# Relay_Board_2nd_Iteration.net
KiCad netlist of a schematic drawn in EAGLE
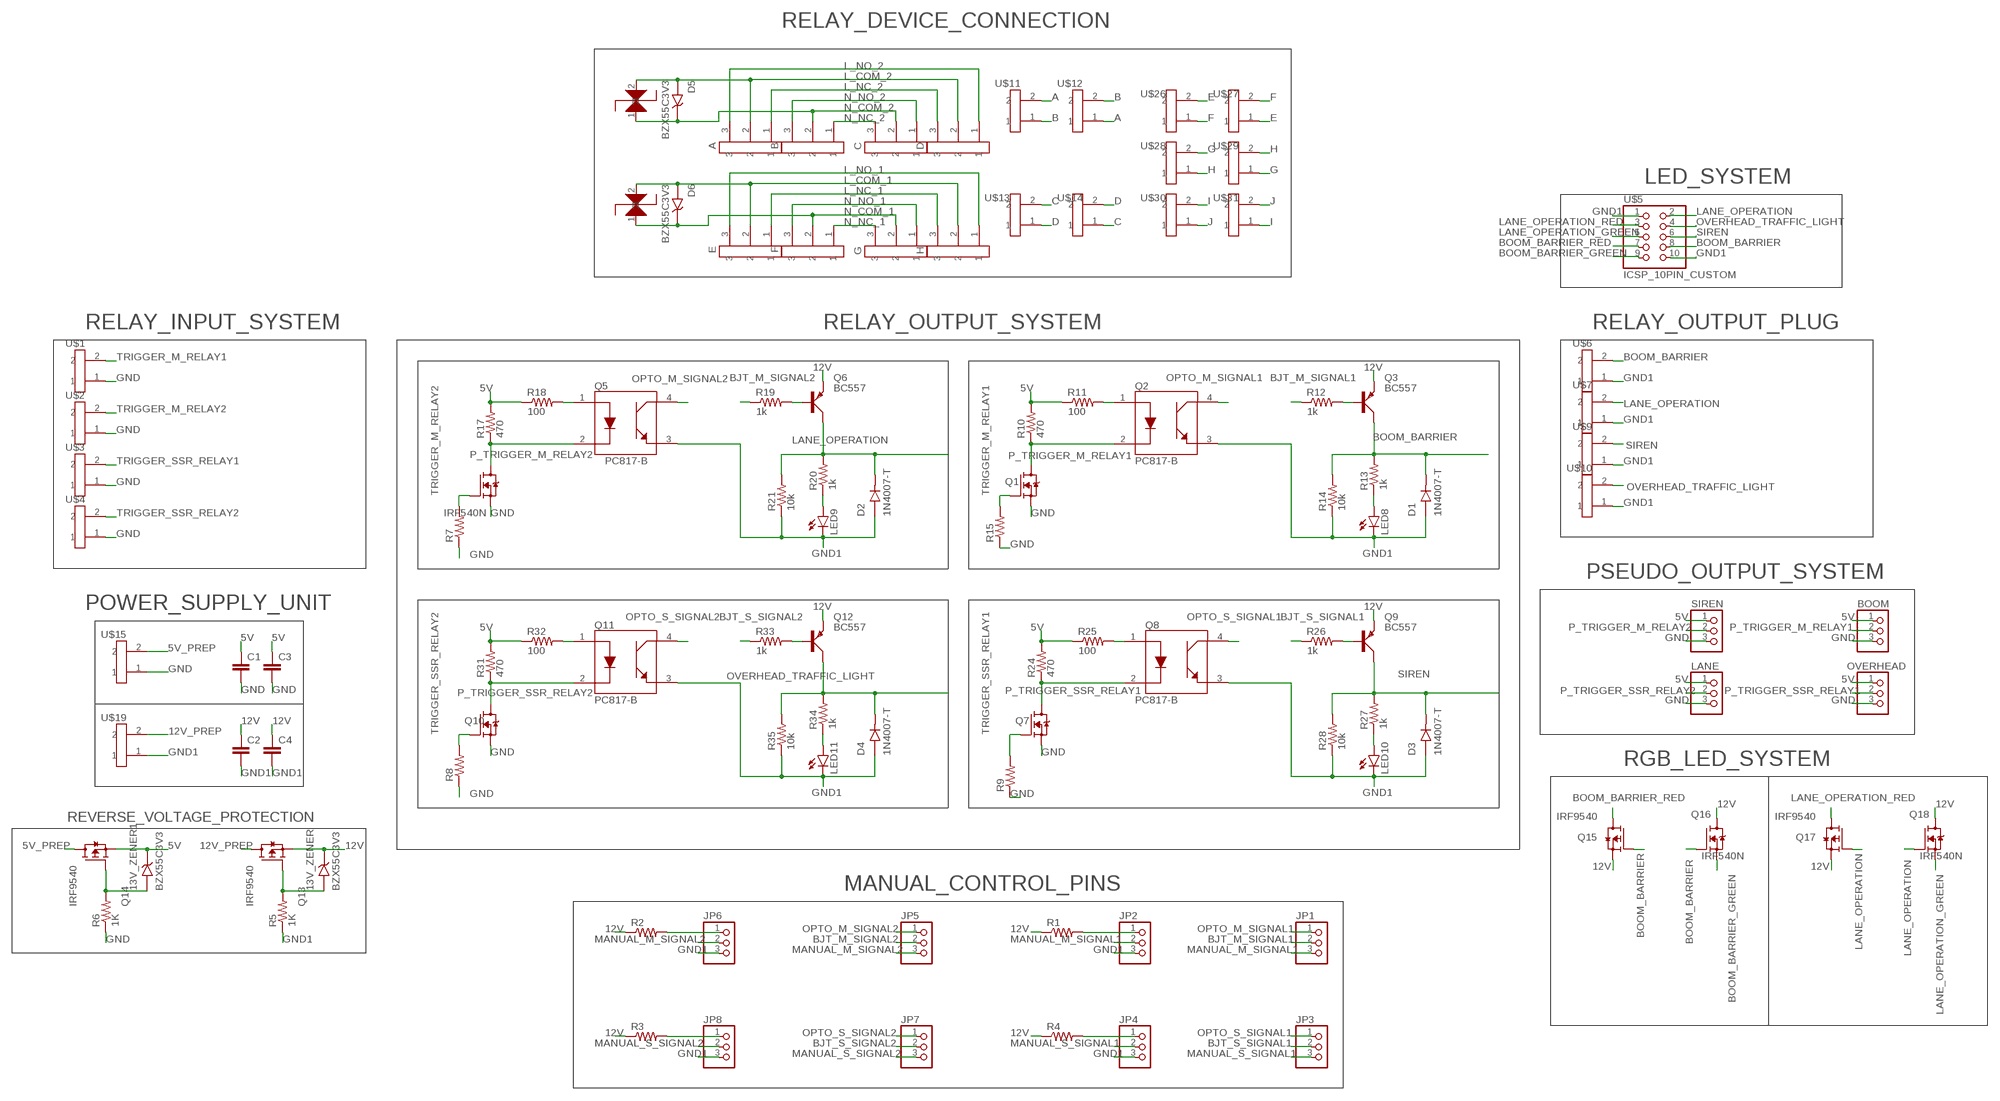
[diagram p0: schematic, sheet 1]

(export (version "E")
  (design (tool "Eeschema 10.0.6"))
  (components
    (comp (ref "13V_ZENER")
      (value "BZX55C3V3")
      (footprint "eagle-import:DIOAD928W47L399D179")
      (fields (field (name "MF") "Vishay Semiconductor") (field (name "MP") "BZX55C3V3-TR"))
      (libsource (lib "eagle-import") (part "BZX55C3V3"))
    )
    (comp (ref "13V_ZENER1")
      (value "BZX55C3V3")
      (footprint "eagle-import:DIOAD928W47L399D179")
      (fields (field (name "MF") "Vishay Semiconductor") (field (name "MP") "BZX55C3V3-TR"))
      (libsource (lib "eagle-import") (part "BZX55C3V3"))
    )
    (comp (ref "A")
      (value "GREEN_PLUG_3")
      (footprint "eagle-import:GREEN_PLUG_3")
      (libsource (lib "eagle-import") (part "GREEN_PLUG_3"))
    )
    (comp (ref "B")
      (value "GREEN_PLUG_3")
      (footprint "eagle-import:GREEN_PLUG_3")
      (libsource (lib "eagle-import") (part "GREEN_PLUG_3"))
    )
    (comp (ref "BOOM")
      (value "PINHD-1X3")
      (footprint "eagle-import:1X03")
      (libsource (lib "eagle-import") (part "PINHD-1X3"))
    )
    (comp (ref "C")
      (value "GREEN_PLUG_90_3")
      (footprint "eagle-import:GREEN_PLUG_90_3")
      (libsource (lib "eagle-import") (part "GREEN_PLUG_90_3"))
    )
    (comp (ref "C1")
      (value "CAPACITOR")
      (footprint "eagle-import:CAPACITOR")
      (libsource (lib "eagle-import") (part "CAPACITOR"))
    )
    (comp (ref "C2")
      (value "CAPACITOR")
      (footprint "eagle-import:CAPACITOR")
      (libsource (lib "eagle-import") (part "CAPACITOR"))
    )
    (comp (ref "C3")
      (value "CAPACITOR")
      (footprint "eagle-import:CAPACITOR")
      (libsource (lib "eagle-import") (part "CAPACITOR"))
    )
    (comp (ref "C4")
      (value "CAPACITOR")
      (footprint "eagle-import:CAPACITOR")
      (libsource (lib "eagle-import") (part "CAPACITOR"))
    )
    (comp (ref "D")
      (value "GREEN_PLUG_90_3")
      (footprint "eagle-import:GREEN_PLUG_90_3")
      (libsource (lib "eagle-import") (part "GREEN_PLUG_90_3"))
    )
    (comp (ref "D1")
      (value "1N4007-T")
      (footprint "eagle-import:DIOAD780W78L463D236")
      (fields (field (name "MF") "Diodes Incorporated"))
      (libsource (lib "eagle-import") (part "1N4007-T"))
    )
    (comp (ref "D2")
      (value "1N4007-T")
      (footprint "eagle-import:DIOAD780W78L463D236")
      (fields (field (name "MF") "Diodes Incorporated"))
      (libsource (lib "eagle-import") (part "1N4007-T"))
    )
    (comp (ref "D3")
      (value "1N4007-T")
      (footprint "eagle-import:DIOAD780W78L463D236")
      (fields (field (name "MF") "Diodes Incorporated"))
      (libsource (lib "eagle-import") (part "1N4007-T"))
    )
    (comp (ref "D4")
      (value "1N4007-T")
      (footprint "eagle-import:DIOAD780W78L463D236")
      (fields (field (name "MF") "Diodes Incorporated"))
      (libsource (lib "eagle-import") (part "1N4007-T"))
    )
    (comp (ref "D5")
      (value "BZX55C3V3")
      (footprint "eagle-import:DIOAD928W47L399D179")
      (fields (field (name "MF") "Vishay Semiconductor") (field (name "MP") "BZX55C3V3-TR"))
      (libsource (lib "eagle-import") (part "BZX55C3V3"))
    )
    (comp (ref "D6")
      (value "BZX55C3V3")
      (footprint "eagle-import:DIOAD928W47L399D179")
      (fields (field (name "MF") "Vishay Semiconductor") (field (name "MP") "BZX55C3V3-TR"))
      (libsource (lib "eagle-import") (part "BZX55C3V3"))
    )
    (comp (ref "E")
      (value "GREEN_PLUG_3")
      (footprint "eagle-import:GREEN_PLUG_3")
      (libsource (lib "eagle-import") (part "GREEN_PLUG_3"))
    )
    (comp (ref "F")
      (value "GREEN_PLUG_3")
      (footprint "eagle-import:GREEN_PLUG_3")
      (libsource (lib "eagle-import") (part "GREEN_PLUG_3"))
    )
    (comp (ref "G")
      (value "GREEN_PLUG_90_3")
      (footprint "eagle-import:GREEN_PLUG_90_3")
      (libsource (lib "eagle-import") (part "GREEN_PLUG_90_3"))
    )
    (comp (ref "H")
      (value "GREEN_PLUG_90_3")
      (footprint "eagle-import:GREEN_PLUG_90_3")
      (libsource (lib "eagle-import") (part "GREEN_PLUG_90_3"))
    )
    (comp (ref "JP1")
      (value "PINHD-1X3")
      (footprint "eagle-import:1X03")
      (libsource (lib "eagle-import") (part "PINHD-1X3"))
    )
    (comp (ref "JP2")
      (value "PINHD-1X3")
      (footprint "eagle-import:1X03")
      (libsource (lib "eagle-import") (part "PINHD-1X3"))
    )
    (comp (ref "JP3")
      (value "PINHD-1X3")
      (footprint "eagle-import:1X03")
      (libsource (lib "eagle-import") (part "PINHD-1X3"))
    )
    (comp (ref "JP4")
      (value "PINHD-1X3")
      (footprint "eagle-import:1X03")
      (libsource (lib "eagle-import") (part "PINHD-1X3"))
    )
    (comp (ref "JP5")
      (value "PINHD-1X3")
      (footprint "eagle-import:1X03")
      (libsource (lib "eagle-import") (part "PINHD-1X3"))
    )
    (comp (ref "JP6")
      (value "PINHD-1X3")
      (footprint "eagle-import:1X03")
      (libsource (lib "eagle-import") (part "PINHD-1X3"))
    )
    (comp (ref "JP7")
      (value "PINHD-1X3")
      (footprint "eagle-import:1X03")
      (libsource (lib "eagle-import") (part "PINHD-1X3"))
    )
    (comp (ref "JP8")
      (value "PINHD-1X3")
      (footprint "eagle-import:1X03")
      (libsource (lib "eagle-import") (part "PINHD-1X3"))
    )
    (comp (ref "LANE")
      (value "PINHD-1X3")
      (footprint "eagle-import:1X03")
      (libsource (lib "eagle-import") (part "PINHD-1X3"))
    )
    (comp (ref "LED8")
      (value "LED")
      (footprint "eagle-import:LED")
      (libsource (lib "eagle-import") (part "LED"))
    )
    (comp (ref "LED9")
      (value "LED")
      (footprint "eagle-import:LED")
      (libsource (lib "eagle-import") (part "LED"))
    )
    (comp (ref "LED10")
      (value "LED")
      (footprint "eagle-import:LED")
      (libsource (lib "eagle-import") (part "LED"))
    )
    (comp (ref "LED11")
      (value "LED")
      (footprint "eagle-import:LED")
      (libsource (lib "eagle-import") (part "LED"))
    )
    (comp (ref "OVERHEAD")
      (value "PINHD-1X3")
      (footprint "eagle-import:1X03")
      (libsource (lib "eagle-import") (part "PINHD-1X3"))
    )
    (comp (ref "Q1")
      (value "IRF540N")
      (footprint "eagle-import:TO254P1054X469X1930-3")
      (fields (field (name "MF") "Infineon Technologies"))
      (libsource (lib "eagle-import") (part "IRF540N"))
    )
    (comp (ref "Q2")
      (value "PC817-B")
      (footprint "eagle-import:DIP762W50P254L650H455Q4B")
      (fields (field (name "MF") "American Bright"))
      (libsource (lib "eagle-import") (part "PC817-B"))
    )
    (comp (ref "Q3")
      (value "BC557")
      (footprint "eagle-import:SOT54A")
      (fields (field (name "MF") "ON Semiconductor"))
      (libsource (lib "eagle-import") (part "BC557"))
    )
    (comp (ref "Q4")
      (value "IRF540N")
      (footprint "eagle-import:TO254P1054X469X1930-3")
      (fields (field (name "MF") "Infineon Technologies"))
      (libsource (lib "eagle-import") (part "IRF540N"))
    )
    (comp (ref "Q5")
      (value "PC817-B")
      (footprint "eagle-import:DIP762W50P254L650H455Q4B")
      (fields (field (name "MF") "American Bright"))
      (libsource (lib "eagle-import") (part "PC817-B"))
    )
    (comp (ref "Q6")
      (value "BC557")
      (footprint "eagle-import:SOT54A")
      (fields (field (name "MF") "ON Semiconductor"))
      (libsource (lib "eagle-import") (part "BC557"))
    )
    (comp (ref "Q7")
      (value "IRF540N")
      (footprint "eagle-import:TO254P1054X469X1930-3")
      (fields (field (name "MF") "Infineon Technologies"))
      (libsource (lib "eagle-import") (part "IRF540N"))
    )
    (comp (ref "Q8")
      (value "PC817-B")
      (footprint "eagle-import:DIP762W50P254L650H455Q4B")
      (fields (field (name "MF") "American Bright"))
      (libsource (lib "eagle-import") (part "PC817-B"))
    )
    (comp (ref "Q9")
      (value "BC557")
      (footprint "eagle-import:SOT54A")
      (fields (field (name "MF") "ON Semiconductor"))
      (libsource (lib "eagle-import") (part "BC557"))
    )
    (comp (ref "Q10")
      (value "IRF540N")
      (footprint "eagle-import:TO254P1054X469X1930-3")
      (fields (field (name "MF") "Infineon Technologies"))
      (libsource (lib "eagle-import") (part "IRF540N"))
    )
    (comp (ref "Q11")
      (value "PC817-B")
      (footprint "eagle-import:DIP762W50P254L650H455Q4B")
      (fields (field (name "MF") "American Bright"))
      (libsource (lib "eagle-import") (part "PC817-B"))
    )
    (comp (ref "Q12")
      (value "BC557")
      (footprint "eagle-import:SOT54A")
      (fields (field (name "MF") "ON Semiconductor"))
      (libsource (lib "eagle-import") (part "BC557"))
    )
    (comp (ref "Q13")
      (value "IRF9540")
      (footprint "eagle-import:TO254P1052X465X1989-3")
      (fields (field (name "MF") "Vishay Siliconix"))
      (libsource (lib "eagle-import") (part "IRF9540"))
    )
    (comp (ref "Q14")
      (value "IRF9540")
      (footprint "eagle-import:TO254P1052X465X1989-3")
      (fields (field (name "MF") "Vishay Siliconix"))
      (libsource (lib "eagle-import") (part "IRF9540"))
    )
    (comp (ref "Q15")
      (value "IRF9540")
      (footprint "eagle-import:TO254P1052X465X1989-3")
      (fields (field (name "MF") "Vishay Siliconix"))
      (libsource (lib "eagle-import") (part "IRF9540"))
    )
    (comp (ref "Q16")
      (value "IRF540N")
      (footprint "eagle-import:TO254P1054X469X1930-3")
      (fields (field (name "MF") "Infineon Technologies"))
      (libsource (lib "eagle-import") (part "IRF540N"))
    )
    (comp (ref "Q17")
      (value "IRF9540")
      (footprint "eagle-import:TO254P1052X465X1989-3")
      (fields (field (name "MF") "Vishay Siliconix"))
      (libsource (lib "eagle-import") (part "IRF9540"))
    )
    (comp (ref "Q18")
      (value "IRF540N")
      (footprint "eagle-import:TO254P1054X469X1930-3")
      (fields (field (name "MF") "Infineon Technologies"))
      (libsource (lib "eagle-import") (part "IRF540N"))
    )
    (comp (ref "R1")
      (value "RESISTOR")
      (footprint "eagle-import:RESISTOR")
      (libsource (lib "eagle-import") (part "RESISTOR"))
    )
    (comp (ref "R2")
      (value "RESISTOR")
      (footprint "eagle-import:RESISTOR")
      (libsource (lib "eagle-import") (part "RESISTOR"))
    )
    (comp (ref "R3")
      (value "RESISTOR")
      (footprint "eagle-import:RESISTOR")
      (libsource (lib "eagle-import") (part "RESISTOR"))
    )
    (comp (ref "R4")
      (value "RESISTOR")
      (footprint "eagle-import:RESISTOR")
      (libsource (lib "eagle-import") (part "RESISTOR"))
    )
    (comp (ref "R5")
      (value "1K")
      (footprint "eagle-import:RESISTOR")
      (libsource (lib "eagle-import") (part "RESISTOR"))
    )
    (comp (ref "R6")
      (value "1K")
      (footprint "eagle-import:RESISTOR")
      (libsource (lib "eagle-import") (part "RESISTOR"))
    )
    (comp (ref "R7")
      (value "RESISTOR")
      (footprint "eagle-import:RESISTOR")
      (libsource (lib "eagle-import") (part "RESISTOR"))
    )
    (comp (ref "R8")
      (value "RESISTOR")
      (footprint "eagle-import:RESISTOR")
      (libsource (lib "eagle-import") (part "RESISTOR"))
    )
    (comp (ref "R9")
      (value "RESISTOR")
      (footprint "eagle-import:RESISTOR")
      (libsource (lib "eagle-import") (part "RESISTOR"))
    )
    (comp (ref "R10")
      (value "470")
      (footprint "eagle-import:RESISTOR")
      (libsource (lib "eagle-import") (part "RESISTOR"))
    )
    (comp (ref "R11")
      (value "100")
      (footprint "eagle-import:RESISTOR")
      (libsource (lib "eagle-import") (part "RESISTOR"))
    )
    (comp (ref "R12")
      (value "1k")
      (footprint "eagle-import:RESISTOR")
      (libsource (lib "eagle-import") (part "RESISTOR"))
    )
    (comp (ref "R13")
      (value "1k")
      (footprint "eagle-import:RESISTOR")
      (libsource (lib "eagle-import") (part "RESISTOR"))
    )
    (comp (ref "R14")
      (value "10k")
      (footprint "eagle-import:RESISTOR")
      (libsource (lib "eagle-import") (part "RESISTOR"))
    )
    (comp (ref "R15")
      (value "RESISTOR")
      (footprint "eagle-import:RESISTOR")
      (libsource (lib "eagle-import") (part "RESISTOR"))
    )
    (comp (ref "R17")
      (value "470")
      (footprint "eagle-import:RESISTOR")
      (libsource (lib "eagle-import") (part "RESISTOR"))
    )
    (comp (ref "R18")
      (value "100")
      (footprint "eagle-import:RESISTOR")
      (libsource (lib "eagle-import") (part "RESISTOR"))
    )
    (comp (ref "R19")
      (value "1k")
      (footprint "eagle-import:RESISTOR")
      (libsource (lib "eagle-import") (part "RESISTOR"))
    )
    (comp (ref "R20")
      (value "1k")
      (footprint "eagle-import:RESISTOR")
      (libsource (lib "eagle-import") (part "RESISTOR"))
    )
    (comp (ref "R21")
      (value "10k")
      (footprint "eagle-import:RESISTOR")
      (libsource (lib "eagle-import") (part "RESISTOR"))
    )
    (comp (ref "R24")
      (value "470")
      (footprint "eagle-import:RESISTOR")
      (libsource (lib "eagle-import") (part "RESISTOR"))
    )
    (comp (ref "R25")
      (value "100")
      (footprint "eagle-import:RESISTOR")
      (libsource (lib "eagle-import") (part "RESISTOR"))
    )
    (comp (ref "R26")
      (value "1k")
      (footprint "eagle-import:RESISTOR")
      (libsource (lib "eagle-import") (part "RESISTOR"))
    )
    (comp (ref "R27")
      (value "1k")
      (footprint "eagle-import:RESISTOR")
      (libsource (lib "eagle-import") (part "RESISTOR"))
    )
    (comp (ref "R28")
      (value "10k")
      (footprint "eagle-import:RESISTOR")
      (libsource (lib "eagle-import") (part "RESISTOR"))
    )
    (comp (ref "R31")
      (value "470")
      (footprint "eagle-import:RESISTOR")
      (libsource (lib "eagle-import") (part "RESISTOR"))
    )
    (comp (ref "R32")
      (value "100")
      (footprint "eagle-import:RESISTOR")
      (libsource (lib "eagle-import") (part "RESISTOR"))
    )
    (comp (ref "R33")
      (value "1k")
      (footprint "eagle-import:RESISTOR")
      (libsource (lib "eagle-import") (part "RESISTOR"))
    )
    (comp (ref "R34")
      (value "1k")
      (footprint "eagle-import:RESISTOR")
      (libsource (lib "eagle-import") (part "RESISTOR"))
    )
    (comp (ref "R35")
      (value "10k")
      (footprint "eagle-import:RESISTOR")
      (libsource (lib "eagle-import") (part "RESISTOR"))
    )
    (comp (ref "SIREN")
      (value "PINHD-1X3")
      (footprint "eagle-import:1X03")
      (libsource (lib "eagle-import") (part "PINHD-1X3"))
    )
    (comp (ref "U$1")
      (value "GREEN_PLUG_90_2")
      (footprint "eagle-import:GREEN_PLUG_90_2")
      (libsource (lib "eagle-import") (part "GREEN_PLUG_90_2"))
    )
    (comp (ref "U$2")
      (value "GREEN_PLUG_90_2")
      (footprint "eagle-import:GREEN_PLUG_90_2")
      (libsource (lib "eagle-import") (part "GREEN_PLUG_90_2"))
    )
    (comp (ref "U$3")
      (value "GREEN_PLUG_90_2")
      (footprint "eagle-import:GREEN_PLUG_90_2")
      (libsource (lib "eagle-import") (part "GREEN_PLUG_90_2"))
    )
    (comp (ref "U$4")
      (value "GREEN_PLUG_90_2")
      (footprint "eagle-import:GREEN_PLUG_90_2")
      (libsource (lib "eagle-import") (part "GREEN_PLUG_90_2"))
    )
    (comp (ref "U$5")
      (value "ICSP_10PIN_CUSTOM")
      (footprint "eagle-import:ICSP_10PIN_CUSTOM")
      (libsource (lib "eagle-import") (part "ICSP_10PIN_CUSTOM"))
    )
    (comp (ref "U$6")
      (value "GREEN_PLUG_2")
      (footprint "eagle-import:GREEN_PLUG_2")
      (libsource (lib "eagle-import") (part "GREEN_PLUG_2"))
    )
    (comp (ref "U$7")
      (value "GREEN_PLUG_2")
      (footprint "eagle-import:GREEN_PLUG_2")
      (libsource (lib "eagle-import") (part "GREEN_PLUG_2"))
    )
    (comp (ref "U$9")
      (value "GREEN_PLUG_2")
      (footprint "eagle-import:GREEN_PLUG_2")
      (libsource (lib "eagle-import") (part "GREEN_PLUG_2"))
    )
    (comp (ref "U$10")
      (value "GREEN_PLUG_2")
      (footprint "eagle-import:GREEN_PLUG_2")
      (libsource (lib "eagle-import") (part "GREEN_PLUG_2"))
    )
    (comp (ref "U$11")
      (value "GREEN_PLUG_2")
      (footprint "eagle-import:GREEN_PLUG_2")
      (libsource (lib "eagle-import") (part "GREEN_PLUG_2"))
    )
    (comp (ref "U$12")
      (value "GREEN_PLUG_90_2")
      (footprint "eagle-import:GREEN_PLUG_90_2")
      (libsource (lib "eagle-import") (part "GREEN_PLUG_90_2"))
    )
    (comp (ref "U$13")
      (value "GREEN_PLUG_90_2")
      (footprint "eagle-import:GREEN_PLUG_90_2")
      (libsource (lib "eagle-import") (part "GREEN_PLUG_90_2"))
    )
    (comp (ref "U$14")
      (value "GREEN_PLUG_2")
      (footprint "eagle-import:GREEN_PLUG_2")
      (libsource (lib "eagle-import") (part "GREEN_PLUG_2"))
    )
    (comp (ref "U$15")
      (value "GREEN_PLUG_90_2")
      (footprint "eagle-import:GREEN_PLUG_90_2")
      (libsource (lib "eagle-import") (part "GREEN_PLUG_90_2"))
    )
    (comp (ref "U$19")
      (value "GREEN_PLUG_90_2")
      (footprint "eagle-import:GREEN_PLUG_90_2")
      (libsource (lib "eagle-import") (part "GREEN_PLUG_90_2"))
    )
    (comp (ref "U$24")
      (value "1KE100A_CUSTOM")
      (footprint "eagle-import:1KE100A_CUSTOM")
      (libsource (lib "eagle-import") (part "1KE100A_CUSTOM"))
    )
    (comp (ref "U$25")
      (value "1KE100A_CUSTOM")
      (footprint "eagle-import:1KE100A_CUSTOM")
      (libsource (lib "eagle-import") (part "1KE100A_CUSTOM"))
    )
    (comp (ref "U$26")
      (value "GREEN_PLUG_2")
      (footprint "eagle-import:GREEN_PLUG_2")
      (libsource (lib "eagle-import") (part "GREEN_PLUG_2"))
    )
    (comp (ref "U$27")
      (value "GREEN_PLUG_90_2")
      (footprint "eagle-import:GREEN_PLUG_90_2")
      (libsource (lib "eagle-import") (part "GREEN_PLUG_90_2"))
    )
    (comp (ref "U$28")
      (value "GREEN_PLUG_2")
      (footprint "eagle-import:GREEN_PLUG_2")
      (libsource (lib "eagle-import") (part "GREEN_PLUG_2"))
    )
    (comp (ref "U$29")
      (value "GREEN_PLUG_90_2")
      (footprint "eagle-import:GREEN_PLUG_90_2")
      (libsource (lib "eagle-import") (part "GREEN_PLUG_90_2"))
    )
    (comp (ref "U$30")
      (value "GREEN_PLUG_2")
      (footprint "eagle-import:GREEN_PLUG_2")
      (libsource (lib "eagle-import") (part "GREEN_PLUG_2"))
    )
    (comp (ref "U$31")
      (value "GREEN_PLUG_90_2")
      (footprint "eagle-import:GREEN_PLUG_90_2")
      (libsource (lib "eagle-import") (part "GREEN_PLUG_90_2"))
    )
  )
  (nets
    (net (code "1") (name "/5V") (class "Default")
      (node (ref "13V_ZENER1") (pin "C") (pinfunction "K_C") (pintype "passive"))
      (node (ref "BOOM") (pin "1") (pinfunction "1_1") (pintype "passive"))
      (node (ref "C1") (pin "1") (pinfunction "1_1") (pintype "passive"))
      (node (ref "C3") (pin "1") (pinfunction "1_1") (pintype "passive"))
      (node (ref "LANE") (pin "1") (pinfunction "1_1") (pintype "passive"))
      (node (ref "OVERHEAD") (pin "1") (pinfunction "1_1") (pintype "passive"))
      (node (ref "Q14") (pin "3") (pinfunction "S_3") (pintype "passive"))
      (node (ref "R10") (pin "2") (pinfunction "2_2") (pintype "passive"))
      (node (ref "R11") (pin "1") (pinfunction "1_1") (pintype "passive"))
      (node (ref "R17") (pin "2") (pinfunction "2_2") (pintype "passive"))
      (node (ref "R18") (pin "1") (pinfunction "1_1") (pintype "passive"))
      (node (ref "R24") (pin "2") (pinfunction "2_2") (pintype "passive"))
      (node (ref "R25") (pin "1") (pinfunction "1_1") (pintype "passive"))
      (node (ref "R31") (pin "2") (pinfunction "2_2") (pintype "passive"))
      (node (ref "R32") (pin "1") (pinfunction "1_1") (pintype "passive"))
      (node (ref "SIREN") (pin "1") (pinfunction "1_1") (pintype "passive"))
    )
    (net (code "2") (name "/5V_PREP") (class "Default")
      (node (ref "Q14") (pin "2") (pinfunction "D_2") (pintype "passive"))
      (node (ref "U$15") (pin "2") (pinfunction "2_2") (pintype "passive"))
    )
    (net (code "3") (name "/12V") (class "Default")
      (node (ref "13V_ZENER") (pin "C") (pinfunction "K_C") (pintype "passive"))
      (node (ref "C2") (pin "1") (pinfunction "1_1") (pintype "passive"))
      (node (ref "C4") (pin "1") (pinfunction "1_1") (pintype "passive"))
      (node (ref "Q12") (pin "E") (pinfunction "E_E") (pintype "passive"))
      (node (ref "Q13") (pin "3") (pinfunction "S_3") (pintype "passive"))
      (node (ref "Q15") (pin "3") (pinfunction "S_3") (pintype "passive"))
      (node (ref "Q16") (pin "2") (pinfunction "D_2") (pintype "passive"))
      (node (ref "Q17") (pin "3") (pinfunction "S_3") (pintype "passive"))
      (node (ref "Q18") (pin "2") (pinfunction "D_2") (pintype "passive"))
      (node (ref "Q3") (pin "E") (pinfunction "E_E") (pintype "passive"))
      (node (ref "Q6") (pin "E") (pinfunction "E_E") (pintype "passive"))
      (node (ref "Q9") (pin "E") (pinfunction "E_E") (pintype "passive"))
      (node (ref "R1") (pin "1") (pinfunction "1_1") (pintype "passive"))
      (node (ref "R2") (pin "1") (pinfunction "1_1") (pintype "passive"))
      (node (ref "R3") (pin "1") (pinfunction "1_1") (pintype "passive"))
      (node (ref "R4") (pin "1") (pinfunction "1_1") (pintype "passive"))
    )
    (net (code "4") (name "/12V_PREP") (class "Default")
      (node (ref "Q13") (pin "2") (pinfunction "D_2") (pintype "passive"))
      (node (ref "U$19") (pin "2") (pinfunction "2_2") (pintype "passive"))
    )
    (net (code "5") (name "/A") (class "Default")
      (node (ref "U$11") (pin "2") (pinfunction "2_2") (pintype "passive"))
      (node (ref "U$12") (pin "1") (pinfunction "1_1") (pintype "passive"))
    )
    (net (code "6") (name "/B") (class "Default")
      (node (ref "U$11") (pin "1") (pinfunction "1_1") (pintype "passive"))
      (node (ref "U$12") (pin "2") (pinfunction "2_2") (pintype "passive"))
    )
    (net (code "7") (name "/BJT_M_SIGNAL1") (class "Default")
      (node (ref "JP1") (pin "2") (pinfunction "2_2") (pintype "passive"))
      (node (ref "R12") (pin "1") (pinfunction "1_1") (pintype "passive"))
    )
    (net (code "8") (name "/BJT_M_SIGNAL2") (class "Default")
      (node (ref "JP5") (pin "2") (pinfunction "2_2") (pintype "passive"))
      (node (ref "R19") (pin "1") (pinfunction "1_1") (pintype "passive"))
    )
    (net (code "9") (name "/BJT_S_SIGNAL1") (class "Default")
      (node (ref "JP3") (pin "2") (pinfunction "2_2") (pintype "passive"))
      (node (ref "R26") (pin "1") (pinfunction "1_1") (pintype "passive"))
    )
    (net (code "10") (name "/BJT_S_SIGNAL2") (class "Default")
      (node (ref "JP7") (pin "2") (pinfunction "2_2") (pintype "passive"))
      (node (ref "R33") (pin "1") (pinfunction "1_1") (pintype "passive"))
    )
    (net (code "11") (name "/BOOM_BARRIER") (class "Default")
      (node (ref "D1") (pin "K") (pinfunction "K_K") (pintype "passive"))
      (node (ref "Q15") (pin "1") (pinfunction "G_1") (pintype "passive"))
      (node (ref "Q16") (pin "1") (pinfunction "G_1") (pintype "passive"))
      (node (ref "Q3") (pin "C") (pinfunction "C_C") (pintype "passive"))
      (node (ref "R13") (pin "2") (pinfunction "2_2") (pintype "passive"))
      (node (ref "R14") (pin "2") (pinfunction "2_2") (pintype "passive"))
      (node (ref "U$5") (pin "8") (pinfunction "8_8") (pintype "passive"))
      (node (ref "U$6") (pin "2") (pinfunction "2_2") (pintype "passive"))
    )
    (net (code "12") (name "/BOOM_BARRIER_GREEN") (class "Default")
      (node (ref "Q16") (pin "3") (pinfunction "S_3") (pintype "passive"))
      (node (ref "U$5") (pin "9") (pinfunction "9_9") (pintype "passive"))
    )
    (net (code "13") (name "/BOOM_BARRIER_RED") (class "Default")
      (node (ref "Q15") (pin "2") (pinfunction "D_2") (pintype "passive"))
      (node (ref "U$5") (pin "7") (pinfunction "7_7") (pintype "passive"))
    )
    (net (code "14") (name "/C") (class "Default")
      (node (ref "U$13") (pin "2") (pinfunction "2_2") (pintype "passive"))
      (node (ref "U$14") (pin "1") (pinfunction "1_1") (pintype "passive"))
    )
    (net (code "15") (name "/D") (class "Default")
      (node (ref "U$13") (pin "1") (pinfunction "1_1") (pintype "passive"))
      (node (ref "U$14") (pin "2") (pinfunction "2_2") (pintype "passive"))
    )
    (net (code "16") (name "/E") (class "Default")
      (node (ref "U$26") (pin "2") (pinfunction "2_2") (pintype "passive"))
      (node (ref "U$27") (pin "1") (pinfunction "1_1") (pintype "passive"))
    )
    (net (code "17") (name "/F") (class "Default")
      (node (ref "U$26") (pin "1") (pinfunction "1_1") (pintype "passive"))
      (node (ref "U$27") (pin "2") (pinfunction "2_2") (pintype "passive"))
    )
    (net (code "18") (name "/G") (class "Default")
      (node (ref "U$28") (pin "2") (pinfunction "2_2") (pintype "passive"))
      (node (ref "U$29") (pin "1") (pinfunction "1_1") (pintype "passive"))
    )
    (net (code "19") (name "/GND") (class "Default")
      (node (ref "BOOM") (pin "3") (pinfunction "3_3") (pintype "passive"))
      (node (ref "C1") (pin "2") (pinfunction "2_2") (pintype "passive"))
      (node (ref "C3") (pin "2") (pinfunction "2_2") (pintype "passive"))
      (node (ref "LANE") (pin "3") (pinfunction "3_3") (pintype "passive"))
      (node (ref "OVERHEAD") (pin "3") (pinfunction "3_3") (pintype "passive"))
      (node (ref "Q1") (pin "3") (pinfunction "S_3") (pintype "passive"))
      (node (ref "Q10") (pin "3") (pinfunction "S_3") (pintype "passive"))
      (node (ref "Q4") (pin "3") (pinfunction "S_3") (pintype "passive"))
      (node (ref "Q7") (pin "3") (pinfunction "S_3") (pintype "passive"))
      (node (ref "R15") (pin "1") (pinfunction "1_1") (pintype "passive"))
      (node (ref "R6") (pin "1") (pinfunction "1_1") (pintype "passive"))
      (node (ref "R7") (pin "1") (pinfunction "1_1") (pintype "passive"))
      (node (ref "R8") (pin "1") (pinfunction "1_1") (pintype "passive"))
      (node (ref "R9") (pin "1") (pinfunction "1_1") (pintype "passive"))
      (node (ref "SIREN") (pin "3") (pinfunction "3_3") (pintype "passive"))
      (node (ref "U$1") (pin "1") (pinfunction "1_1") (pintype "passive"))
      (node (ref "U$15") (pin "1") (pinfunction "1_1") (pintype "passive"))
      (node (ref "U$2") (pin "1") (pinfunction "1_1") (pintype "passive"))
      (node (ref "U$3") (pin "1") (pinfunction "1_1") (pintype "passive"))
      (node (ref "U$4") (pin "1") (pinfunction "1_1") (pintype "passive"))
    )
    (net (code "20") (name "/GND1") (class "Default")
      (node (ref "C2") (pin "2") (pinfunction "2_2") (pintype "passive"))
      (node (ref "C4") (pin "2") (pinfunction "2_2") (pintype "passive"))
      (node (ref "D1") (pin "A") (pinfunction "A_A") (pintype "passive"))
      (node (ref "D2") (pin "A") (pinfunction "A_A") (pintype "passive"))
      (node (ref "D3") (pin "A") (pinfunction "A_A") (pintype "passive"))
      (node (ref "D4") (pin "A") (pinfunction "A_A") (pintype "passive"))
      (node (ref "JP2") (pin "3") (pinfunction "3_3") (pintype "passive"))
      (node (ref "JP4") (pin "3") (pinfunction "3_3") (pintype "passive"))
      (node (ref "JP6") (pin "3") (pinfunction "3_3") (pintype "passive"))
      (node (ref "JP8") (pin "3") (pinfunction "3_3") (pintype "passive"))
      (node (ref "LED10") (pin "K") (pinfunction "C_K") (pintype "passive"))
      (node (ref "LED11") (pin "K") (pinfunction "C_K") (pintype "passive"))
      (node (ref "LED8") (pin "K") (pinfunction "C_K") (pintype "passive"))
      (node (ref "LED9") (pin "K") (pinfunction "C_K") (pintype "passive"))
      (node (ref "Q11") (pin "3") (pinfunction "EMITTER_3") (pintype "passive"))
      (node (ref "Q2") (pin "3") (pinfunction "EMITTER_3") (pintype "passive"))
      (node (ref "Q5") (pin "3") (pinfunction "EMITTER_3") (pintype "passive"))
      (node (ref "Q8") (pin "3") (pinfunction "EMITTER_3") (pintype "passive"))
      (node (ref "R14") (pin "1") (pinfunction "1_1") (pintype "passive"))
      (node (ref "R21") (pin "1") (pinfunction "1_1") (pintype "passive"))
      (node (ref "R28") (pin "1") (pinfunction "1_1") (pintype "passive"))
      (node (ref "R35") (pin "1") (pinfunction "1_1") (pintype "passive"))
      (node (ref "R5") (pin "1") (pinfunction "1_1") (pintype "passive"))
      (node (ref "U$10") (pin "1") (pinfunction "1_1") (pintype "passive"))
      (node (ref "U$19") (pin "1") (pinfunction "1_1") (pintype "passive"))
      (node (ref "U$5") (pin "1") (pinfunction "1_1") (pintype "passive"))
      (node (ref "U$5") (pin "10") (pinfunction "10_10") (pintype "passive"))
      (node (ref "U$6") (pin "1") (pinfunction "1_1") (pintype "passive"))
      (node (ref "U$7") (pin "1") (pinfunction "1_1") (pintype "passive"))
      (node (ref "U$9") (pin "1") (pinfunction "1_1") (pintype "passive"))
    )
    (net (code "21") (name "/H") (class "Default")
      (node (ref "U$28") (pin "1") (pinfunction "1_1") (pintype "passive"))
      (node (ref "U$29") (pin "2") (pinfunction "2_2") (pintype "passive"))
    )
    (net (code "22") (name "/I") (class "Default")
      (node (ref "U$30") (pin "2") (pinfunction "2_2") (pintype "passive"))
      (node (ref "U$31") (pin "1") (pinfunction "1_1") (pintype "passive"))
    )
    (net (code "23") (name "/J") (class "Default")
      (node (ref "U$30") (pin "1") (pinfunction "1_1") (pintype "passive"))
      (node (ref "U$31") (pin "2") (pinfunction "2_2") (pintype "passive"))
    )
    (net (code "24") (name "/LANE_OPERATION") (class "Default")
      (node (ref "D2") (pin "K") (pinfunction "K_K") (pintype "passive"))
      (node (ref "Q17") (pin "1") (pinfunction "G_1") (pintype "passive"))
      (node (ref "Q18") (pin "1") (pinfunction "G_1") (pintype "passive"))
      (node (ref "Q6") (pin "C") (pinfunction "C_C") (pintype "passive"))
      (node (ref "R20") (pin "2") (pinfunction "2_2") (pintype "passive"))
      (node (ref "R21") (pin "2") (pinfunction "2_2") (pintype "passive"))
      (node (ref "U$5") (pin "2") (pinfunction "2_2") (pintype "passive"))
      (node (ref "U$7") (pin "2") (pinfunction "2_2") (pintype "passive"))
    )
    (net (code "25") (name "/LANE_OPERATION_GREEN") (class "Default")
      (node (ref "Q18") (pin "3") (pinfunction "S_3") (pintype "passive"))
      (node (ref "U$5") (pin "5") (pinfunction "5_5") (pintype "passive"))
    )
    (net (code "26") (name "/LANE_OPERATION_RED") (class "Default")
      (node (ref "Q17") (pin "2") (pinfunction "D_2") (pintype "passive"))
      (node (ref "U$5") (pin "3") (pinfunction "3_3") (pintype "passive"))
    )
    (net (code "27") (name "/L_COM_1") (class "Default")
      (node (ref "D6") (pin "A") (pinfunction "A_A") (pintype "passive"))
      (node (ref "E") (pin "2") (pinfunction "2_2") (pintype "passive"))
      (node (ref "H") (pin "2") (pinfunction "2_2") (pintype "passive"))
      (node (ref "U$25") (pin "2") (pinfunction "2_2") (pintype "bidirectional"))
    )
    (net (code "28") (name "/L_COM_2") (class "Default")
      (node (ref "A") (pin "2") (pinfunction "2_2") (pintype "passive"))
      (node (ref "D") (pin "2") (pinfunction "2_2") (pintype "passive"))
      (node (ref "D5") (pin "A") (pinfunction "A_A") (pintype "passive"))
      (node (ref "U$24") (pin "2") (pinfunction "2_2") (pintype "bidirectional"))
    )
    (net (code "29") (name "/L_NC_1") (class "Default")
      (node (ref "E") (pin "1") (pinfunction "1_1") (pintype "passive"))
      (node (ref "H") (pin "3") (pinfunction "3_3") (pintype "passive"))
    )
    (net (code "30") (name "/L_NC_2") (class "Default")
      (node (ref "A") (pin "1") (pinfunction "1_1") (pintype "passive"))
      (node (ref "D") (pin "3") (pinfunction "3_3") (pintype "passive"))
    )
    (net (code "31") (name "/L_NO_1") (class "Default")
      (node (ref "E") (pin "3") (pinfunction "3_3") (pintype "passive"))
      (node (ref "H") (pin "1") (pinfunction "1_1") (pintype "passive"))
    )
    (net (code "32") (name "/L_NO_2") (class "Default")
      (node (ref "A") (pin "3") (pinfunction "3_3") (pintype "passive"))
      (node (ref "D") (pin "1") (pinfunction "1_1") (pintype "passive"))
    )
    (net (code "33") (name "/MANUAL_M_SIGNAL1") (class "Default")
      (node (ref "JP1") (pin "3") (pinfunction "3_3") (pintype "passive"))
      (node (ref "JP2") (pin "2") (pinfunction "2_2") (pintype "passive"))
    )
    (net (code "34") (name "/MANUAL_M_SIGNAL2") (class "Default")
      (node (ref "JP5") (pin "3") (pinfunction "3_3") (pintype "passive"))
      (node (ref "JP6") (pin "2") (pinfunction "2_2") (pintype "passive"))
    )
    (net (code "35") (name "/MANUAL_S_SIGNAL1") (class "Default")
      (node (ref "JP3") (pin "3") (pinfunction "3_3") (pintype "passive"))
      (node (ref "JP4") (pin "2") (pinfunction "2_2") (pintype "passive"))
    )
    (net (code "36") (name "/MANUAL_S_SIGNAL2") (class "Default")
      (node (ref "JP7") (pin "3") (pinfunction "3_3") (pintype "passive"))
      (node (ref "JP8") (pin "2") (pinfunction "2_2") (pintype "passive"))
    )
    (net (code "37") (name "/N_COM_1") (class "Default")
      (node (ref "D6") (pin "C") (pinfunction "K_C") (pintype "passive"))
      (node (ref "F") (pin "2") (pinfunction "2_2") (pintype "passive"))
      (node (ref "G") (pin "2") (pinfunction "2_2") (pintype "passive"))
      (node (ref "U$25") (pin "1") (pinfunction "1_1") (pintype "bidirectional"))
    )
    (net (code "38") (name "/N_COM_2") (class "Default")
      (node (ref "B") (pin "2") (pinfunction "2_2") (pintype "passive"))
      (node (ref "C") (pin "2") (pinfunction "2_2") (pintype "passive"))
      (node (ref "D5") (pin "C") (pinfunction "K_C") (pintype "passive"))
      (node (ref "U$24") (pin "1") (pinfunction "1_1") (pintype "bidirectional"))
    )
    (net (code "39") (name "/N_NC_1") (class "Default")
      (node (ref "F") (pin "1") (pinfunction "1_1") (pintype "passive"))
      (node (ref "G") (pin "3") (pinfunction "3_3") (pintype "passive"))
    )
    (net (code "40") (name "/N_NC_2") (class "Default")
      (node (ref "B") (pin "1") (pinfunction "1_1") (pintype "passive"))
      (node (ref "C") (pin "3") (pinfunction "3_3") (pintype "passive"))
    )
    (net (code "41") (name "/N_NO_1") (class "Default")
      (node (ref "F") (pin "3") (pinfunction "3_3") (pintype "passive"))
      (node (ref "G") (pin "1") (pinfunction "1_1") (pintype "passive"))
    )
    (net (code "42") (name "/N_NO_2") (class "Default")
      (node (ref "B") (pin "3") (pinfunction "3_3") (pintype "passive"))
      (node (ref "C") (pin "1") (pinfunction "1_1") (pintype "passive"))
    )
    (net (code "43") (name "/OPTO_M_SIGNAL1") (class "Default")
      (node (ref "JP1") (pin "1") (pinfunction "1_1") (pintype "passive"))
      (node (ref "Q2") (pin "4") (pinfunction "COLLECTOR_4") (pintype "passive"))
    )
    (net (code "44") (name "/OPTO_M_SIGNAL2") (class "Default")
      (node (ref "JP5") (pin "1") (pinfunction "1_1") (pintype "passive"))
      (node (ref "Q5") (pin "4") (pinfunction "COLLECTOR_4") (pintype "passive"))
    )
    (net (code "45") (name "/OPTO_S_SIGNAL1") (class "Default")
      (node (ref "JP3") (pin "1") (pinfunction "1_1") (pintype "passive"))
      (node (ref "Q8") (pin "4") (pinfunction "COLLECTOR_4") (pintype "passive"))
    )
    (net (code "46") (name "/OPTO_S_SIGNAL2") (class "Default")
      (node (ref "JP7") (pin "1") (pinfunction "1_1") (pintype "passive"))
      (node (ref "Q11") (pin "4") (pinfunction "COLLECTOR_4") (pintype "passive"))
    )
    (net (code "47") (name "/OVERHEAD_TRAFFIC_LIGHT") (class "Default")
      (node (ref "D4") (pin "K") (pinfunction "K_K") (pintype "passive"))
      (node (ref "Q12") (pin "C") (pinfunction "C_C") (pintype "passive"))
      (node (ref "R34") (pin "2") (pinfunction "2_2") (pintype "passive"))
      (node (ref "R35") (pin "2") (pinfunction "2_2") (pintype "passive"))
      (node (ref "U$10") (pin "2") (pinfunction "2_2") (pintype "passive"))
      (node (ref "U$5") (pin "4") (pinfunction "4_4") (pintype "passive"))
    )
    (net (code "48") (name "/P_TRIGGER_M_RELAY1") (class "Default")
      (node (ref "BOOM") (pin "2") (pinfunction "2_2") (pintype "passive"))
      (node (ref "Q1") (pin "2") (pinfunction "D_2") (pintype "passive"))
      (node (ref "Q2") (pin "2") (pinfunction "CATHODE_2") (pintype "passive"))
      (node (ref "R10") (pin "1") (pinfunction "1_1") (pintype "passive"))
    )
    (net (code "49") (name "/P_TRIGGER_M_RELAY2") (class "Default")
      (node (ref "Q4") (pin "2") (pinfunction "D_2") (pintype "passive"))
      (node (ref "Q5") (pin "2") (pinfunction "CATHODE_2") (pintype "passive"))
      (node (ref "R17") (pin "1") (pinfunction "1_1") (pintype "passive"))
      (node (ref "SIREN") (pin "2") (pinfunction "2_2") (pintype "passive"))
    )
    (net (code "50") (name "/P_TRIGGER_SSR_RELAY1") (class "Default")
      (node (ref "OVERHEAD") (pin "2") (pinfunction "2_2") (pintype "passive"))
      (node (ref "Q7") (pin "2") (pinfunction "D_2") (pintype "passive"))
      (node (ref "Q8") (pin "2") (pinfunction "CATHODE_2") (pintype "passive"))
      (node (ref "R24") (pin "1") (pinfunction "1_1") (pintype "passive"))
    )
    (net (code "51") (name "/P_TRIGGER_SSR_RELAY2") (class "Default")
      (node (ref "LANE") (pin "2") (pinfunction "2_2") (pintype "passive"))
      (node (ref "Q10") (pin "2") (pinfunction "D_2") (pintype "passive"))
      (node (ref "Q11") (pin "2") (pinfunction "CATHODE_2") (pintype "passive"))
      (node (ref "R31") (pin "1") (pinfunction "1_1") (pintype "passive"))
    )
    (net (code "52") (name "/SIREN") (class "Default")
      (node (ref "D3") (pin "K") (pinfunction "K_K") (pintype "passive"))
      (node (ref "Q9") (pin "C") (pinfunction "C_C") (pintype "passive"))
      (node (ref "R27") (pin "2") (pinfunction "2_2") (pintype "passive"))
      (node (ref "R28") (pin "2") (pinfunction "2_2") (pintype "passive"))
      (node (ref "U$5") (pin "6") (pinfunction "6_6") (pintype "passive"))
      (node (ref "U$9") (pin "2") (pinfunction "2_2") (pintype "passive"))
    )
    (net (code "53") (name "/TRIGGER_M_RELAY1") (class "Default")
      (node (ref "Q1") (pin "1") (pinfunction "G_1") (pintype "passive"))
      (node (ref "R15") (pin "2") (pinfunction "2_2") (pintype "passive"))
      (node (ref "U$1") (pin "2") (pinfunction "2_2") (pintype "passive"))
    )
    (net (code "54") (name "/TRIGGER_M_RELAY2") (class "Default")
      (node (ref "Q4") (pin "1") (pinfunction "G_1") (pintype "passive"))
      (node (ref "R7") (pin "2") (pinfunction "2_2") (pintype "passive"))
      (node (ref "U$2") (pin "2") (pinfunction "2_2") (pintype "passive"))
    )
    (net (code "55") (name "/TRIGGER_SSR_RELAY1") (class "Default")
      (node (ref "Q7") (pin "1") (pinfunction "G_1") (pintype "passive"))
      (node (ref "R9") (pin "2") (pinfunction "2_2") (pintype "passive"))
      (node (ref "U$3") (pin "2") (pinfunction "2_2") (pintype "passive"))
    )
    (net (code "56") (name "/TRIGGER_SSR_RELAY2") (class "Default")
      (node (ref "Q10") (pin "1") (pinfunction "G_1") (pintype "passive"))
      (node (ref "R8") (pin "2") (pinfunction "2_2") (pintype "passive"))
      (node (ref "U$4") (pin "2") (pinfunction "2_2") (pintype "passive"))
    )
    (net (code "57") (name "Net-(JP2-Pad1)") (class "Default")
      (node (ref "JP2") (pin "1") (pinfunction "1_1") (pintype "passive"))
      (node (ref "R1") (pin "2") (pinfunction "2_2") (pintype "passive"))
    )
    (net (code "58") (name "Net-(JP4-Pad1)") (class "Default")
      (node (ref "JP4") (pin "1") (pinfunction "1_1") (pintype "passive"))
      (node (ref "R4") (pin "2") (pinfunction "2_2") (pintype "passive"))
    )
    (net (code "59") (name "Net-(JP6-Pad1)") (class "Default")
      (node (ref "JP6") (pin "1") (pinfunction "1_1") (pintype "passive"))
      (node (ref "R2") (pin "2") (pinfunction "2_2") (pintype "passive"))
    )
    (net (code "60") (name "Net-(JP8-Pad1)") (class "Default")
      (node (ref "JP8") (pin "1") (pinfunction "1_1") (pintype "passive"))
      (node (ref "R3") (pin "2") (pinfunction "2_2") (pintype "passive"))
    )
    (net (code "61") (name "Net-(LED8-PadA)") (class "Default")
      (node (ref "LED8") (pin "A") (pinfunction "A_A") (pintype "passive"))
      (node (ref "R13") (pin "1") (pinfunction "1_1") (pintype "passive"))
    )
    (net (code "62") (name "Net-(LED9-PadA)") (class "Default")
      (node (ref "LED9") (pin "A") (pinfunction "A_A") (pintype "passive"))
      (node (ref "R20") (pin "1") (pinfunction "1_1") (pintype "passive"))
    )
    (net (code "63") (name "Net-(LED10-PadA)") (class "Default")
      (node (ref "LED10") (pin "A") (pinfunction "A_A") (pintype "passive"))
      (node (ref "R27") (pin "1") (pinfunction "1_1") (pintype "passive"))
    )
    (net (code "64") (name "Net-(LED11-PadA)") (class "Default")
      (node (ref "LED11") (pin "A") (pinfunction "A_A") (pintype "passive"))
      (node (ref "R34") (pin "1") (pinfunction "1_1") (pintype "passive"))
    )
    (net (code "65") (name "Net-(Q2-ANODE)") (class "Default")
      (node (ref "Q2") (pin "1") (pinfunction "ANODE_1") (pintype "passive"))
      (node (ref "R11") (pin "2") (pinfunction "2_2") (pintype "passive"))
    )
    (net (code "66") (name "Net-(Q3-PadB)") (class "Default")
      (node (ref "Q3") (pin "B") (pinfunction "B_B") (pintype "passive"))
      (node (ref "R12") (pin "2") (pinfunction "2_2") (pintype "passive"))
    )
    (net (code "67") (name "Net-(Q5-ANODE)") (class "Default")
      (node (ref "Q5") (pin "1") (pinfunction "ANODE_1") (pintype "passive"))
      (node (ref "R18") (pin "2") (pinfunction "2_2") (pintype "passive"))
    )
    (net (code "68") (name "Net-(Q6-PadB)") (class "Default")
      (node (ref "Q6") (pin "B") (pinfunction "B_B") (pintype "passive"))
      (node (ref "R19") (pin "2") (pinfunction "2_2") (pintype "passive"))
    )
    (net (code "69") (name "Net-(Q8-ANODE)") (class "Default")
      (node (ref "Q8") (pin "1") (pinfunction "ANODE_1") (pintype "passive"))
      (node (ref "R25") (pin "2") (pinfunction "2_2") (pintype "passive"))
    )
    (net (code "70") (name "Net-(Q9-PadB)") (class "Default")
      (node (ref "Q9") (pin "B") (pinfunction "B_B") (pintype "passive"))
      (node (ref "R26") (pin "2") (pinfunction "2_2") (pintype "passive"))
    )
    (net (code "71") (name "Net-(Q11-ANODE)") (class "Default")
      (node (ref "Q11") (pin "1") (pinfunction "ANODE_1") (pintype "passive"))
      (node (ref "R32") (pin "2") (pinfunction "2_2") (pintype "passive"))
    )
    (net (code "72") (name "Net-(Q12-PadB)") (class "Default")
      (node (ref "Q12") (pin "B") (pinfunction "B_B") (pintype "passive"))
      (node (ref "R33") (pin "2") (pinfunction "2_2") (pintype "passive"))
    )
    (net (code "73") (name "Net-(Q13-G)") (class "Default")
      (node (ref "13V_ZENER") (pin "A") (pinfunction "A_A") (pintype "passive"))
      (node (ref "Q13") (pin "1") (pinfunction "G_1") (pintype "passive"))
      (node (ref "R5") (pin "2") (pinfunction "2_2") (pintype "passive"))
    )
    (net (code "74") (name "Net-(Q14-G)") (class "Default")
      (node (ref "13V_ZENER1") (pin "A") (pinfunction "A_A") (pintype "passive"))
      (node (ref "Q14") (pin "1") (pinfunction "G_1") (pintype "passive"))
      (node (ref "R6") (pin "2") (pinfunction "2_2") (pintype "passive"))
    )
  )
)
